# PCIE_Connector.net
KiCad netlist of a schematic drawn in Altium Designer
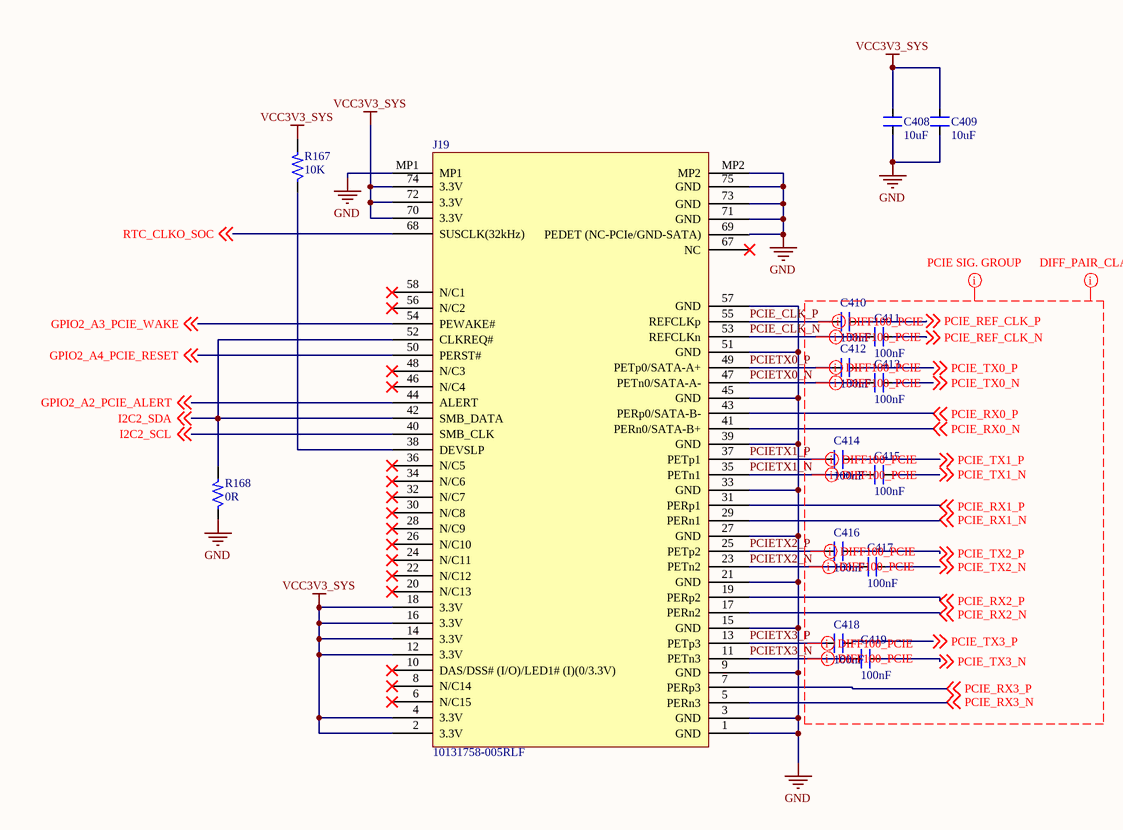
[diagram p0: PCIE Connector.SchDoc]

(export (version "E")
  (design (tool "Eeschema 10.0.6"))
  (components
    (comp (ref "C408")
      (value "10uF")
      (footprint "CAP_0603")
      (description "10µF ±10% 10V Ceramic Capacitor X5R 0603 (1608 Metric)")
      (fields
        (field (name "MANUFACTURER PART NUMBER") "GRM188R61A106KE69J")
        (field (name "MANUFACTURER") "Murata Electronics")
      )
      (libsource (lib "RK3399 _Module_Schlib") (part "CAP_10uF-10V-10%-0603"))
    )
    (comp (ref "C409")
      (value "10uF")
      (footprint "CAP_0603")
      (description "10µF ±10% 10V Ceramic Capacitor X5R 0603 (1608 Metric)")
      (fields
        (field (name "MANUFACTURER PART NUMBER") "GRM188R61A106KE69J")
        (field (name "MANUFACTURER") "Murata Electronics")
      )
      (libsource (lib "RK3399 _Module_Schlib") (part "CAP_10uF-10V-10%-0603"))
    )
    (comp (ref "C410")
      (value "100nF")
      (footprint "CAP_0402")
      (description "0.1µF ±10% 10V Ceramic Capacitor X7R 0402 (1005 Metric)")
      (fields
        (field (name "MANUFACTURER") "Yageo")
        (field (name "MANUFACTURER PART NUMBER") "CC0402KRX7R6BB104")
      )
      (libsource (lib "RK3399 _Module_Schlib") (part "CAP_100nF-10V-10%-0402"))
    )
    (comp (ref "C411")
      (value "100nF")
      (footprint "CAP_0402")
      (description "0.1µF ±10% 10V Ceramic Capacitor X7R 0402 (1005 Metric)")
      (fields
        (field (name "MANUFACTURER") "Yageo")
        (field (name "MANUFACTURER PART NUMBER") "CC0402KRX7R6BB104")
      )
      (libsource (lib "RK3399 _Module_Schlib") (part "CAP_100nF-10V-10%-0402"))
    )
    (comp (ref "C412")
      (value "100nF")
      (footprint "CAP_0402")
      (description "0.1µF ±10% 10V Ceramic Capacitor X7R 0402 (1005 Metric)")
      (fields
        (field (name "MANUFACTURER") "Yageo")
        (field (name "MANUFACTURER PART NUMBER") "CC0402KRX7R6BB104")
      )
      (libsource (lib "RK3399 _Module_Schlib") (part "CAP_100nF-10V-10%-0402"))
    )
    (comp (ref "C413")
      (value "100nF")
      (footprint "CAP_0402")
      (description "0.1µF ±10% 10V Ceramic Capacitor X7R 0402 (1005 Metric)")
      (fields
        (field (name "MANUFACTURER") "Yageo")
        (field (name "MANUFACTURER PART NUMBER") "CC0402KRX7R6BB104")
      )
      (libsource (lib "RK3399 _Module_Schlib") (part "CAP_100nF-10V-10%-0402"))
    )
    (comp (ref "C414")
      (value "100nF")
      (footprint "CAP_0402")
      (description "0.1µF ±10% 10V Ceramic Capacitor X7R 0402 (1005 Metric)")
      (fields
        (field (name "MANUFACTURER") "Yageo")
        (field (name "MANUFACTURER PART NUMBER") "CC0402KRX7R6BB104")
      )
      (libsource (lib "RK3399 _Module_Schlib") (part "CAP_100nF-10V-10%-0402"))
    )
    (comp (ref "C415")
      (value "100nF")
      (footprint "CAP_0402")
      (description "0.1µF ±10% 10V Ceramic Capacitor X7R 0402 (1005 Metric)")
      (fields
        (field (name "MANUFACTURER") "Yageo")
        (field (name "MANUFACTURER PART NUMBER") "CC0402KRX7R6BB104")
      )
      (libsource (lib "RK3399 _Module_Schlib") (part "CAP_100nF-10V-10%-0402"))
    )
    (comp (ref "C416")
      (value "100nF")
      (footprint "CAP_0402")
      (description "0.1µF ±10% 10V Ceramic Capacitor X7R 0402 (1005 Metric)")
      (fields
        (field (name "MANUFACTURER") "Yageo")
        (field (name "MANUFACTURER PART NUMBER") "CC0402KRX7R6BB104")
      )
      (libsource (lib "RK3399 _Module_Schlib") (part "CAP_100nF-10V-10%-0402"))
    )
    (comp (ref "C417")
      (value "100nF")
      (footprint "CAP_0402")
      (description "0.1µF ±10% 10V Ceramic Capacitor X7R 0402 (1005 Metric)")
      (fields
        (field (name "MANUFACTURER") "Yageo")
        (field (name "MANUFACTURER PART NUMBER") "CC0402KRX7R6BB104")
      )
      (libsource (lib "RK3399 _Module_Schlib") (part "CAP_100nF-10V-10%-0402"))
    )
    (comp (ref "C418")
      (value "100nF")
      (footprint "CAP_0402")
      (description "0.1µF ±10% 10V Ceramic Capacitor X7R 0402 (1005 Metric)")
      (fields
        (field (name "MANUFACTURER") "Yageo")
        (field (name "MANUFACTURER PART NUMBER") "CC0402KRX7R6BB104")
      )
      (libsource (lib "RK3399 _Module_Schlib") (part "CAP_100nF-10V-10%-0402"))
    )
    (comp (ref "C419")
      (value "100nF")
      (footprint "CAP_0402")
      (description "0.1µF ±10% 10V Ceramic Capacitor X7R 0402 (1005 Metric)")
      (fields
        (field (name "MANUFACTURER") "Yageo")
        (field (name "MANUFACTURER PART NUMBER") "CC0402KRX7R6BB104")
      )
      (libsource (lib "RK3399 _Module_Schlib") (part "CAP_100nF-10V-10%-0402"))
    )
    (comp (ref "J19")
      (value "10131758-005RLF")
      (footprint "PCIE_10131758-005RLF")
      (description "PCI Express/PCI Connectors M.2 connector, 8.5H, M key")
      (fields (field (name "MANUFACTURER") "Amphenol ICC (FCI)"))
      (libsource (lib "EsteemPCB_COB_Course_schlib") (part "CON-PLG_67X1-10131758-005RLF-SMD"))
    )
    (comp (ref "R167")
      (value "10K")
      (footprint "RES_0603")
      (description "10 kOhms ±1% 0.1W, 1/10W Chip Resistor 0603 (1608 Metric) Thick Film")
      (fields
        (field (name "MANUFACTURER") "Yageo")
        (field (name "MANUFACTURER PART NUMBER") "RC0603FR-0710KL")
      )
      (libsource (lib "RK3399 _Module_Schlib") (part "RES_10K-0.1W-1%-0603"))
    )
    (comp (ref "R168")
      (value "0R")
      (footprint "RES_0603")
      (description "0 Ohms Jumper 0.1W, 1/10W Chip Resistor 0603 (1608 Metric) Thick Film")
      (fields
        (field (name "MANUFACTURER") "Yageo")
        (field (name "MANUFACTURER PART NUMBER") "RC0603JR-070RL")
      )
      (libsource (lib "RK3399 _Module_Schlib") (part "RES_0R-0.1W-1%-0603"))
    )
  )
  (nets
    (net (code "1") (name "/PCIETX0_N") (class "Default")
      (node (ref "C413") (pin "1") (pinfunction "1_1") (pintype "passive"))
      (node (ref "J19") (pin "47") (pinfunction "PETn0/SATA-A-_47") (pintype "passive"))
    )
    (net (code "2") (name "/PCIETX0_P") (class "Default")
      (node (ref "C412") (pin "1") (pinfunction "1_1") (pintype "passive"))
      (node (ref "J19") (pin "49") (pinfunction "PETp0/SATA-A+_49") (pintype "passive"))
    )
    (net (code "3") (name "/PCIETX1_N") (class "Default")
      (node (ref "C415") (pin "1") (pinfunction "1_1") (pintype "passive"))
      (node (ref "J19") (pin "35") (pinfunction "PETn1_35") (pintype "passive"))
    )
    (net (code "4") (name "/PCIETX1_P") (class "Default")
      (node (ref "C414") (pin "1") (pinfunction "1_1") (pintype "passive"))
      (node (ref "J19") (pin "37") (pinfunction "PETp1_37") (pintype "passive"))
    )
    (net (code "5") (name "/PCIETX2_N") (class "Default")
      (node (ref "C417") (pin "1") (pinfunction "1_1") (pintype "passive"))
      (node (ref "J19") (pin "23") (pinfunction "PETn2_23") (pintype "passive"))
    )
    (net (code "6") (name "/PCIETX2_P") (class "Default")
      (node (ref "C416") (pin "1") (pinfunction "1_1") (pintype "passive"))
      (node (ref "J19") (pin "25") (pinfunction "PETp2_25") (pintype "passive"))
    )
    (net (code "7") (name "/PCIETX3_N") (class "Default")
      (node (ref "C419") (pin "1") (pinfunction "1_1") (pintype "passive"))
      (node (ref "J19") (pin "11") (pinfunction "PETn3_11") (pintype "passive"))
    )
    (net (code "8") (name "/PCIETX3_P") (class "Default")
      (node (ref "C418") (pin "1") (pinfunction "1_1") (pintype "passive"))
      (node (ref "J19") (pin "13") (pinfunction "PETp3_13") (pintype "passive"))
    )
    (net (code "9") (name "/PCIE_CLK_N") (class "Default")
      (node (ref "C411") (pin "1") (pinfunction "1_1") (pintype "passive"))
      (node (ref "J19") (pin "53") (pinfunction "REFCLKn_53") (pintype "passive"))
    )
    (net (code "10") (name "/PCIE_CLK_P") (class "Default")
      (node (ref "C410") (pin "1") (pinfunction "1_1") (pintype "passive"))
      (node (ref "J19") (pin "55") (pinfunction "REFCLKp_55") (pintype "passive"))
    )
    (net (code "11") (name "GND") (class "Default")
      (node (ref "C408") (pin "1") (pinfunction "1_1") (pintype "passive"))
      (node (ref "C409") (pin "1") (pinfunction "1_1") (pintype "passive"))
      (node (ref "J19") (pin "1") (pinfunction "GND_1") (pintype "passive"))
      (node (ref "J19") (pin "15") (pinfunction "GND_15") (pintype "passive"))
      (node (ref "J19") (pin "21") (pinfunction "GND_21") (pintype "passive"))
      (node (ref "J19") (pin "27") (pinfunction "GND_27") (pintype "passive"))
      (node (ref "J19") (pin "3") (pinfunction "GND_3") (pintype "passive"))
      (node (ref "J19") (pin "33") (pinfunction "GND_33") (pintype "passive"))
      (node (ref "J19") (pin "39") (pinfunction "GND_39") (pintype "passive"))
      (node (ref "J19") (pin "45") (pinfunction "GND_45") (pintype "passive"))
      (node (ref "J19") (pin "51") (pinfunction "GND_51") (pintype "passive"))
      (node (ref "J19") (pin "57") (pinfunction "GND_57") (pintype "passive"))
      (node (ref "J19") (pin "69") (pinfunction "PEDET_(NC-PCIe/GND-SATA)_69") (pintype "passive"))
      (node (ref "J19") (pin "71") (pinfunction "GND_71") (pintype "passive"))
      (node (ref "J19") (pin "73") (pinfunction "GND_73") (pintype "passive"))
      (node (ref "J19") (pin "75") (pinfunction "GND_75") (pintype "passive"))
      (node (ref "J19") (pin "9") (pinfunction "GND_9") (pintype "passive"))
      (node (ref "J19") (pin "MP1") (pinfunction "MP1_MP1") (pintype "passive"))
      (node (ref "J19") (pin "MP2") (pinfunction "MP2_MP2") (pintype "passive"))
      (node (ref "R168") (pin "1") (pinfunction "1_1") (pintype "passive"))
    )
    (net (code "12") (name "GPIO2_A2_PCIE_ALERT") (class "Default")
      (node (ref "J19") (pin "44") (pinfunction "ALERT_44") (pintype "passive"))
    )
    (net (code "13") (name "GPIO2_A3_PCIE_WAKE") (class "Default")
      (node (ref "J19") (pin "54") (pinfunction "PEWAKE#_54") (pintype "passive"))
    )
    (net (code "14") (name "GPIO2_A4_PCIE_RESET") (class "Default")
      (node (ref "J19") (pin "50") (pinfunction "PERST#_50") (pintype "passive"))
    )
    (net (code "15") (name "I2C2_SCL") (class "Default")
      (node (ref "J19") (pin "40") (pinfunction "SMB_CLK_40") (pintype "passive"))
    )
    (net (code "16") (name "I2C2_SDA") (class "Default")
      (node (ref "J19") (pin "42") (pinfunction "SMB_DATA_42") (pintype "passive"))
      (node (ref "J19") (pin "52") (pinfunction "CLKREQ#_52") (pintype "passive"))
      (node (ref "R168") (pin "2") (pinfunction "2_2") (pintype "passive"))
    )
    (net (code "17") (name "Net-(J19-DEVSLP)") (class "Default")
      (node (ref "J19") (pin "38") (pinfunction "DEVSLP_38") (pintype "passive"))
      (node (ref "R167") (pin "1") (pinfunction "1_1") (pintype "passive"))
    )
    (net (code "18") (name "PCIE_REF_CLK_N") (class "Default")
      (node (ref "C411") (pin "2") (pinfunction "2_2") (pintype "passive"))
    )
    (net (code "19") (name "PCIE_REF_CLK_P") (class "Default")
      (node (ref "C410") (pin "2") (pinfunction "2_2") (pintype "passive"))
    )
    (net (code "20") (name "PCIE_RX0_N") (class "Default")
      (node (ref "J19") (pin "41") (pinfunction "PERn0/SATA-B+_41") (pintype "passive"))
    )
    (net (code "21") (name "PCIE_RX0_P") (class "Default")
      (node (ref "J19") (pin "43") (pinfunction "PERp0/SATA-B-_43") (pintype "passive"))
    )
    (net (code "22") (name "PCIE_RX1_N") (class "Default")
      (node (ref "J19") (pin "29") (pinfunction "PERn1_29") (pintype "passive"))
    )
    (net (code "23") (name "PCIE_RX1_P") (class "Default")
      (node (ref "J19") (pin "31") (pinfunction "PERp1_31") (pintype "passive"))
    )
    (net (code "24") (name "PCIE_RX2_N") (class "Default")
      (node (ref "J19") (pin "17") (pinfunction "PERn2_17") (pintype "passive"))
    )
    (net (code "25") (name "PCIE_RX2_P") (class "Default")
      (node (ref "J19") (pin "19") (pinfunction "PERp2_19") (pintype "passive"))
    )
    (net (code "26") (name "PCIE_RX3_N") (class "Default")
      (node (ref "J19") (pin "5") (pinfunction "PERn3_5") (pintype "passive"))
    )
    (net (code "27") (name "PCIE_RX3_P") (class "Default")
      (node (ref "J19") (pin "7") (pinfunction "PERp3_7") (pintype "passive"))
    )
    (net (code "28") (name "PCIE_TX0_N") (class "Default")
      (node (ref "C413") (pin "2") (pinfunction "2_2") (pintype "passive"))
    )
    (net (code "29") (name "PCIE_TX0_P") (class "Default")
      (node (ref "C412") (pin "2") (pinfunction "2_2") (pintype "passive"))
    )
    (net (code "30") (name "PCIE_TX1_N") (class "Default")
      (node (ref "C415") (pin "2") (pinfunction "2_2") (pintype "passive"))
    )
    (net (code "31") (name "PCIE_TX1_P") (class "Default")
      (node (ref "C414") (pin "2") (pinfunction "2_2") (pintype "passive"))
    )
    (net (code "32") (name "PCIE_TX2_N") (class "Default")
      (node (ref "C417") (pin "2") (pinfunction "2_2") (pintype "passive"))
    )
    (net (code "33") (name "PCIE_TX2_P") (class "Default")
      (node (ref "C416") (pin "2") (pinfunction "2_2") (pintype "passive"))
    )
    (net (code "34") (name "PCIE_TX3_N") (class "Default")
      (node (ref "C419") (pin "2") (pinfunction "2_2") (pintype "passive"))
    )
    (net (code "35") (name "PCIE_TX3_P") (class "Default")
      (node (ref "C418") (pin "2") (pinfunction "2_2") (pintype "passive"))
    )
    (net (code "36") (name "RTC_CLKO_SOC") (class "Default")
      (node (ref "J19") (pin "68") (pinfunction "SUSCLK(32kHz)_68") (pintype "passive"))
    )
    (net (code "37") (name "VCC3V3_SYS") (class "Default")
      (node (ref "C408") (pin "2") (pinfunction "2_2") (pintype "passive"))
      (node (ref "C409") (pin "2") (pinfunction "2_2") (pintype "passive"))
      (node (ref "J19") (pin "12") (pinfunction "3.3V_12") (pintype "passive"))
      (node (ref "J19") (pin "14") (pinfunction "3.3V_14") (pintype "passive"))
      (node (ref "J19") (pin "16") (pinfunction "3.3V_16") (pintype "passive"))
      (node (ref "J19") (pin "18") (pinfunction "3.3V_18") (pintype "passive"))
      (node (ref "J19") (pin "2") (pinfunction "3.3V_2") (pintype "passive"))
      (node (ref "J19") (pin "4") (pinfunction "3.3V_4") (pintype "passive"))
      (node (ref "J19") (pin "70") (pinfunction "3.3V_70") (pintype "passive"))
      (node (ref "J19") (pin "72") (pinfunction "3.3V_72") (pintype "passive"))
      (node (ref "J19") (pin "74") (pinfunction "3.3V_74") (pintype "passive"))
      (node (ref "R167") (pin "2") (pinfunction "2_2") (pintype "passive"))
    )
    (net (code "38") (name "unconnected-(J19-DAS{slash}DSS#_(I{slash}O){slash}LED1#_(I)(0{slash}3.3V)-Pad10)") (class "Default")
      (node (ref "J19") (pin "10") (pinfunction "DAS/DSS#_(I/O)/LED1#_(I)(0/3.3V)_10") (pintype "passive+no_connect"))
    )
    (net (code "39") (name "unconnected-(J19-NC-Pad67)") (class "Default")
      (node (ref "J19") (pin "67") (pinfunction "NC_67") (pintype "passive+no_connect"))
    )
    (net (code "40") (name "unconnected-(J19-N{slash}C1-Pad58)") (class "Default")
      (node (ref "J19") (pin "58") (pinfunction "N/C1_58") (pintype "passive+no_connect"))
    )
    (net (code "41") (name "unconnected-(J19-N{slash}C2-Pad56)") (class "Default")
      (node (ref "J19") (pin "56") (pinfunction "N/C2_56") (pintype "passive+no_connect"))
    )
    (net (code "42") (name "unconnected-(J19-N{slash}C3-Pad48)") (class "Default")
      (node (ref "J19") (pin "48") (pinfunction "N/C3_48") (pintype "passive+no_connect"))
    )
    (net (code "43") (name "unconnected-(J19-N{slash}C4-Pad46)") (class "Default")
      (node (ref "J19") (pin "46") (pinfunction "N/C4_46") (pintype "passive+no_connect"))
    )
    (net (code "44") (name "unconnected-(J19-N{slash}C5-Pad36)") (class "Default")
      (node (ref "J19") (pin "36") (pinfunction "N/C5_36") (pintype "passive+no_connect"))
    )
    (net (code "45") (name "unconnected-(J19-N{slash}C6-Pad34)") (class "Default")
      (node (ref "J19") (pin "34") (pinfunction "N/C6_34") (pintype "passive+no_connect"))
    )
    (net (code "46") (name "unconnected-(J19-N{slash}C7-Pad32)") (class "Default")
      (node (ref "J19") (pin "32") (pinfunction "N/C7_32") (pintype "passive+no_connect"))
    )
    (net (code "47") (name "unconnected-(J19-N{slash}C8-Pad30)") (class "Default")
      (node (ref "J19") (pin "30") (pinfunction "N/C8_30") (pintype "passive+no_connect"))
    )
    (net (code "48") (name "unconnected-(J19-N{slash}C9-Pad28)") (class "Default")
      (node (ref "J19") (pin "28") (pinfunction "N/C9_28") (pintype "passive+no_connect"))
    )
    (net (code "49") (name "unconnected-(J19-N{slash}C10-Pad26)") (class "Default")
      (node (ref "J19") (pin "26") (pinfunction "N/C10_26") (pintype "passive+no_connect"))
    )
    (net (code "50") (name "unconnected-(J19-N{slash}C11-Pad24)") (class "Default")
      (node (ref "J19") (pin "24") (pinfunction "N/C11_24") (pintype "passive+no_connect"))
    )
    (net (code "51") (name "unconnected-(J19-N{slash}C12-Pad22)") (class "Default")
      (node (ref "J19") (pin "22") (pinfunction "N/C12_22") (pintype "passive+no_connect"))
    )
    (net (code "52") (name "unconnected-(J19-N{slash}C13-Pad20)") (class "Default")
      (node (ref "J19") (pin "20") (pinfunction "N/C13_20") (pintype "passive+no_connect"))
    )
    (net (code "53") (name "unconnected-(J19-N{slash}C14-Pad8)") (class "Default")
      (node (ref "J19") (pin "8") (pinfunction "N/C14_8") (pintype "passive+no_connect"))
    )
    (net (code "54") (name "unconnected-(J19-N{slash}C15-Pad6)") (class "Default")
      (node (ref "J19") (pin "6") (pinfunction "N/C15_6") (pintype "passive+no_connect"))
    )
  )
)
